# DM1097_TopLevel.net
KiCad netlist of a schematic drawn in Altium Designer
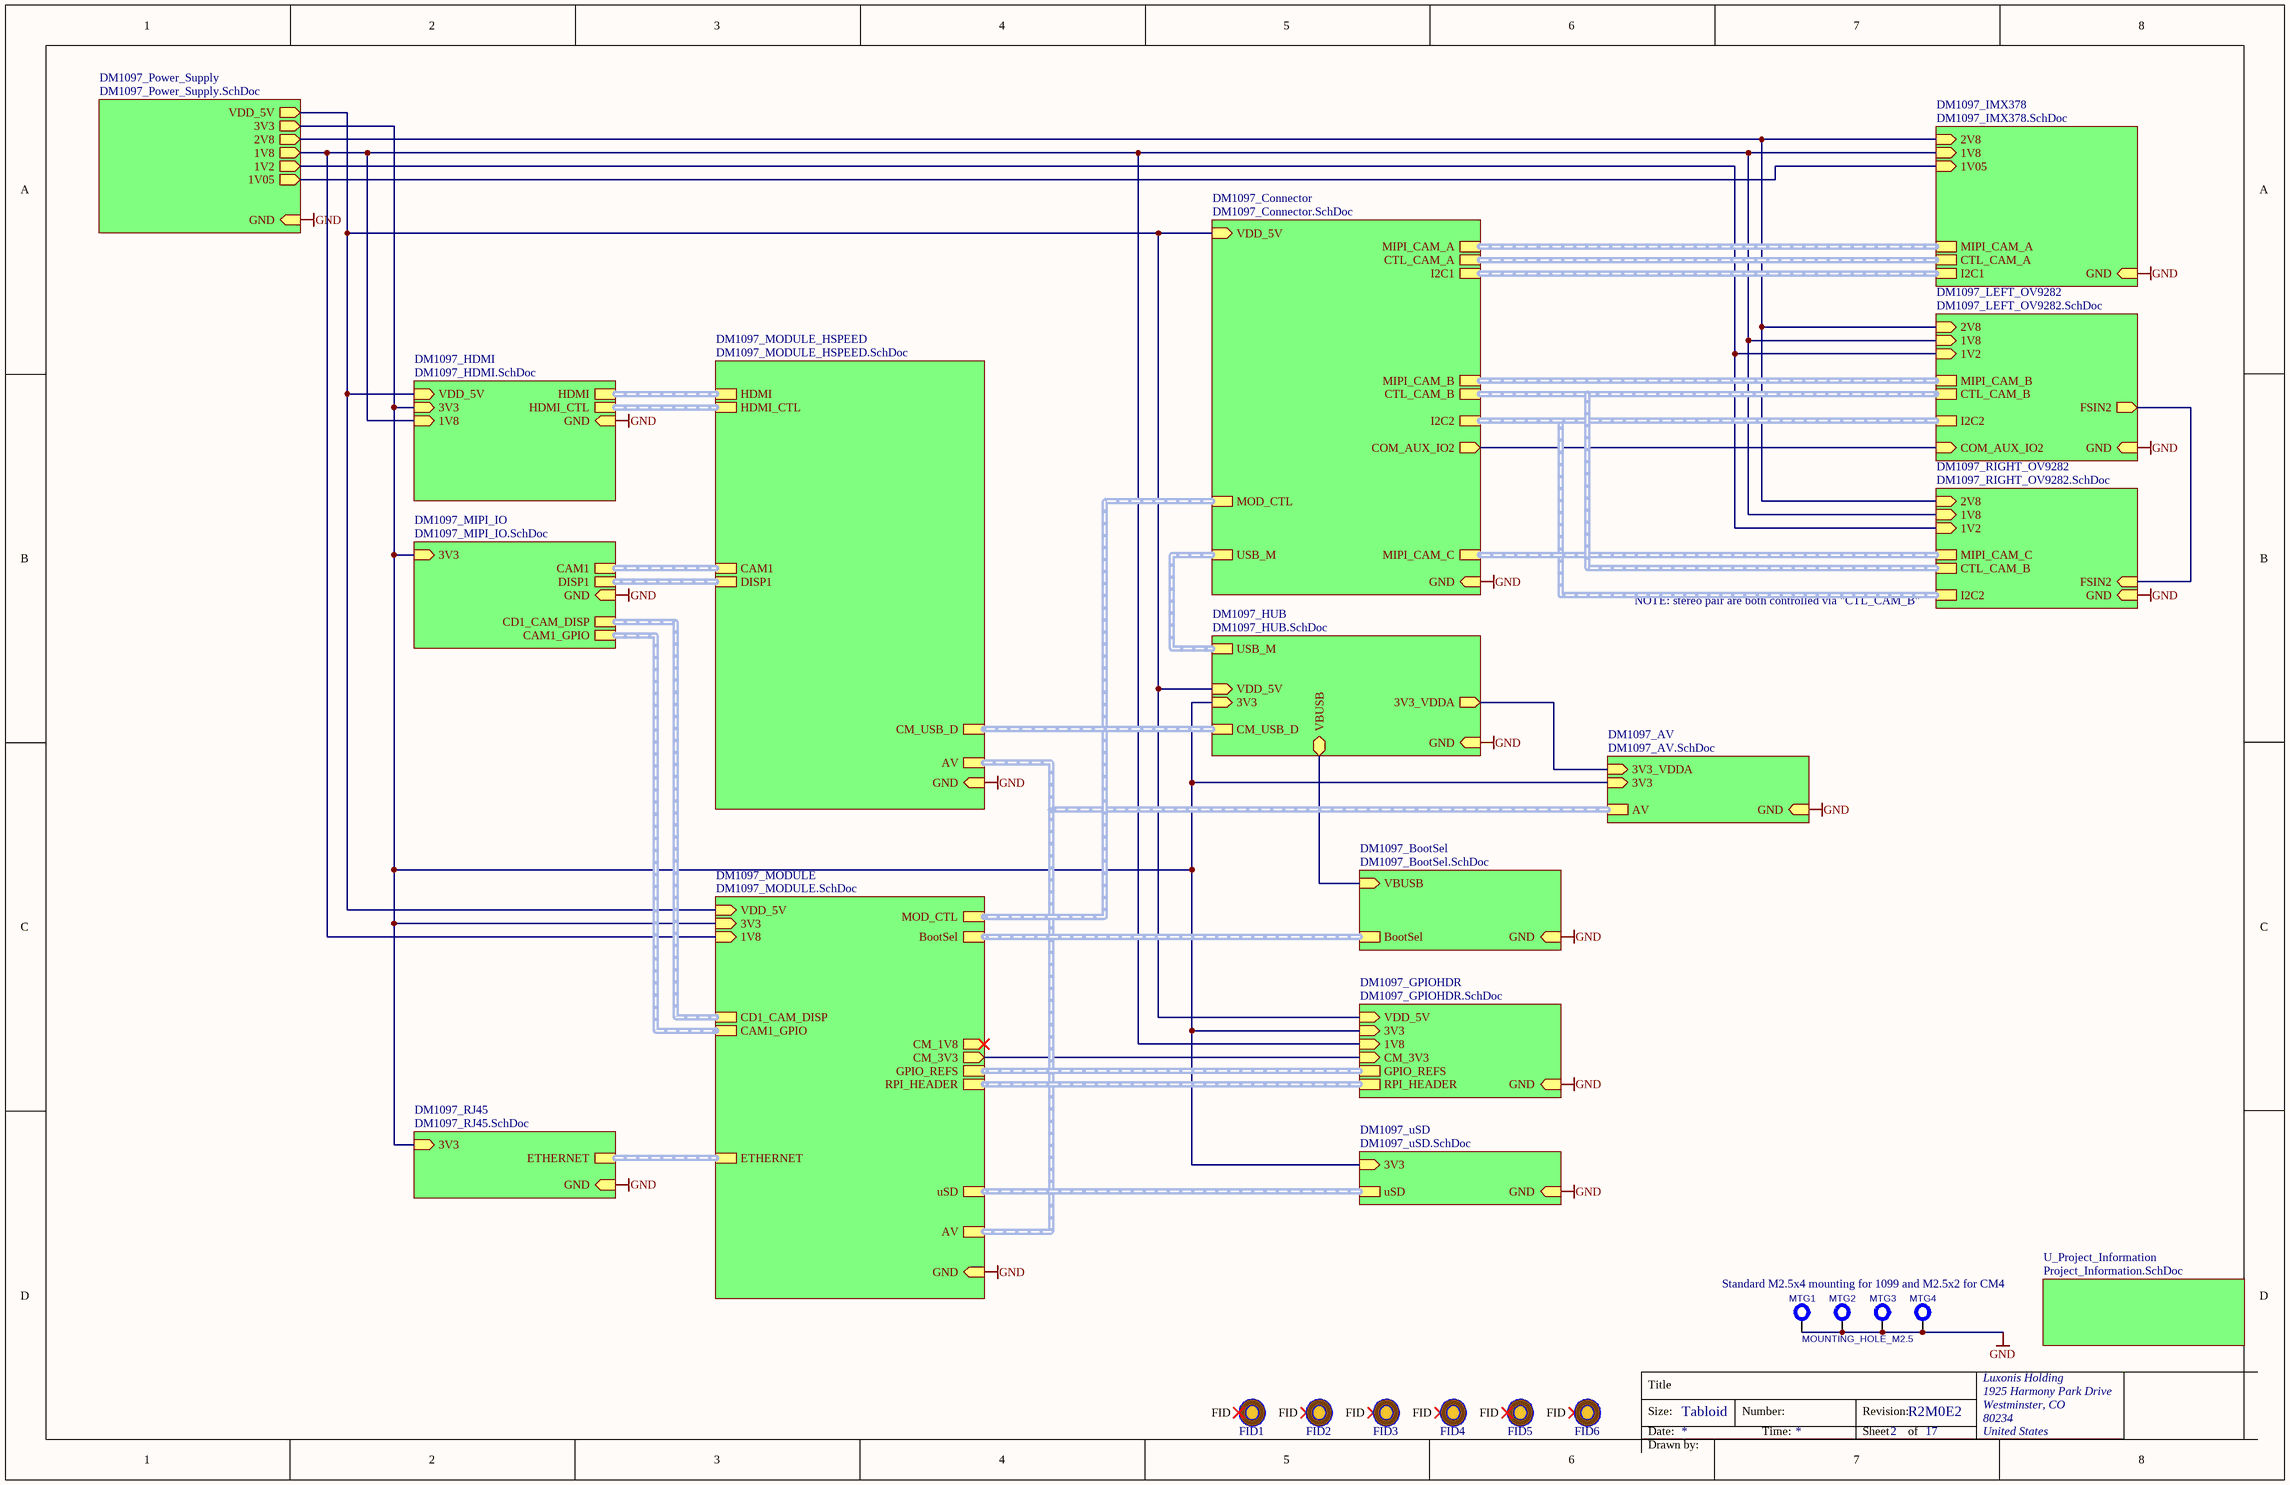
[diagram p0: DM1097_TopLevel.SchDoc]

(export (version "E")
  (design (tool "Eeschema 10.0.6"))
  (components
    (comp (ref "FID1")
      (value "~")
      (footprint "LuxonisMaster:FIDUCIAL_ROUND_1MM")
      (description "Fiducial with various available footprints")
      (libsource (lib "LuxonisMaster") (part "FIDUCIAL"))
    )
    (comp (ref "FID2")
      (value "~")
      (footprint "LuxonisMaster:FIDUCIAL_ROUND_1MM")
      (description "Fiducial with various available footprints")
      (libsource (lib "LuxonisMaster") (part "FIDUCIAL"))
    )
    (comp (ref "FID3")
      (value "~")
      (footprint "LuxonisMaster:FIDUCIAL_ROUND_1MM")
      (description "Fiducial with various available footprints")
      (libsource (lib "LuxonisMaster") (part "FIDUCIAL"))
    )
    (comp (ref "FID4")
      (value "~")
      (footprint "LuxonisMaster:FIDUCIAL_ROUND_1MM")
      (description "Fiducial with various available footprints")
      (libsource (lib "LuxonisMaster") (part "FIDUCIAL"))
    )
    (comp (ref "FID5")
      (value "~")
      (footprint "LuxonisMaster:FIDUCIAL_ROUND_1MM")
      (description "Fiducial with various available footprints")
      (libsource (lib "LuxonisMaster") (part "FIDUCIAL"))
    )
    (comp (ref "FID6")
      (value "~")
      (footprint "LuxonisMaster:FIDUCIAL_ROUND_1MM")
      (description "Fiducial with various available footprints")
      (libsource (lib "LuxonisMaster") (part "FIDUCIAL"))
    )
    (comp (ref "MTG1")
      (value "~")
      (footprint "LuxonisMaster:MOUNTING_HOLE_M2.5")
      (description "=CurrentFootprint")
      (libsource (lib "LuxonisMaster") (part "MP_Mounting-Holes"))
    )
    (comp (ref "MTG2")
      (value "~")
      (footprint "LuxonisMaster:MOUNTING_HOLE_M2.5")
      (description "=CurrentFootprint")
      (libsource (lib "LuxonisMaster") (part "MP_Mounting-Holes"))
    )
    (comp (ref "MTG3")
      (value "~")
      (footprint "LuxonisMaster:MOUNTING_HOLE_M2.5")
      (description "=CurrentFootprint")
      (libsource (lib "LuxonisMaster") (part "MP_Mounting-Holes"))
    )
    (comp (ref "MTG4")
      (value "~")
      (footprint "LuxonisMaster:MOUNTING_HOLE_M2.5")
      (description "=CurrentFootprint")
      (libsource (lib "LuxonisMaster") (part "MP_Mounting-Holes"))
    )
  )
  (nets
    (net (code "35") (name "GND") (class "Default")
      (node (ref "MTG1") (pin "1") (pintype "passive"))
      (node (ref "MTG2") (pin "1") (pintype "passive"))
      (node (ref "MTG3") (pin "1") (pintype "passive"))
      (node (ref "MTG4") (pin "1") (pintype "passive"))
    )
    (net (code "36") (name "unconnected-(FID1-PadFID)") (class "Default")
      (node (ref "FID1") (pin "FID") (pinfunction "FID_FID") (pintype "input+no_connect"))
    )
    (net (code "37") (name "unconnected-(FID2-PadFID)") (class "Default")
      (node (ref "FID2") (pin "FID") (pinfunction "FID_FID") (pintype "input+no_connect"))
    )
    (net (code "38") (name "unconnected-(FID3-PadFID)") (class "Default")
      (node (ref "FID3") (pin "FID") (pinfunction "FID_FID") (pintype "input+no_connect"))
    )
    (net (code "39") (name "unconnected-(FID4-PadFID)") (class "Default")
      (node (ref "FID4") (pin "FID") (pinfunction "FID_FID") (pintype "input+no_connect"))
    )
    (net (code "40") (name "unconnected-(FID5-PadFID)") (class "Default")
      (node (ref "FID5") (pin "FID") (pinfunction "FID_FID") (pintype "input+no_connect"))
    )
    (net (code "41") (name "unconnected-(FID6-PadFID)") (class "Default")
      (node (ref "FID6") (pin "FID") (pinfunction "FID_FID") (pintype "input+no_connect"))
    )
  )
)
